# brick_i2c_3axis_MMA8451.net
KiCad netlist of a schematic drawn in EAGLE
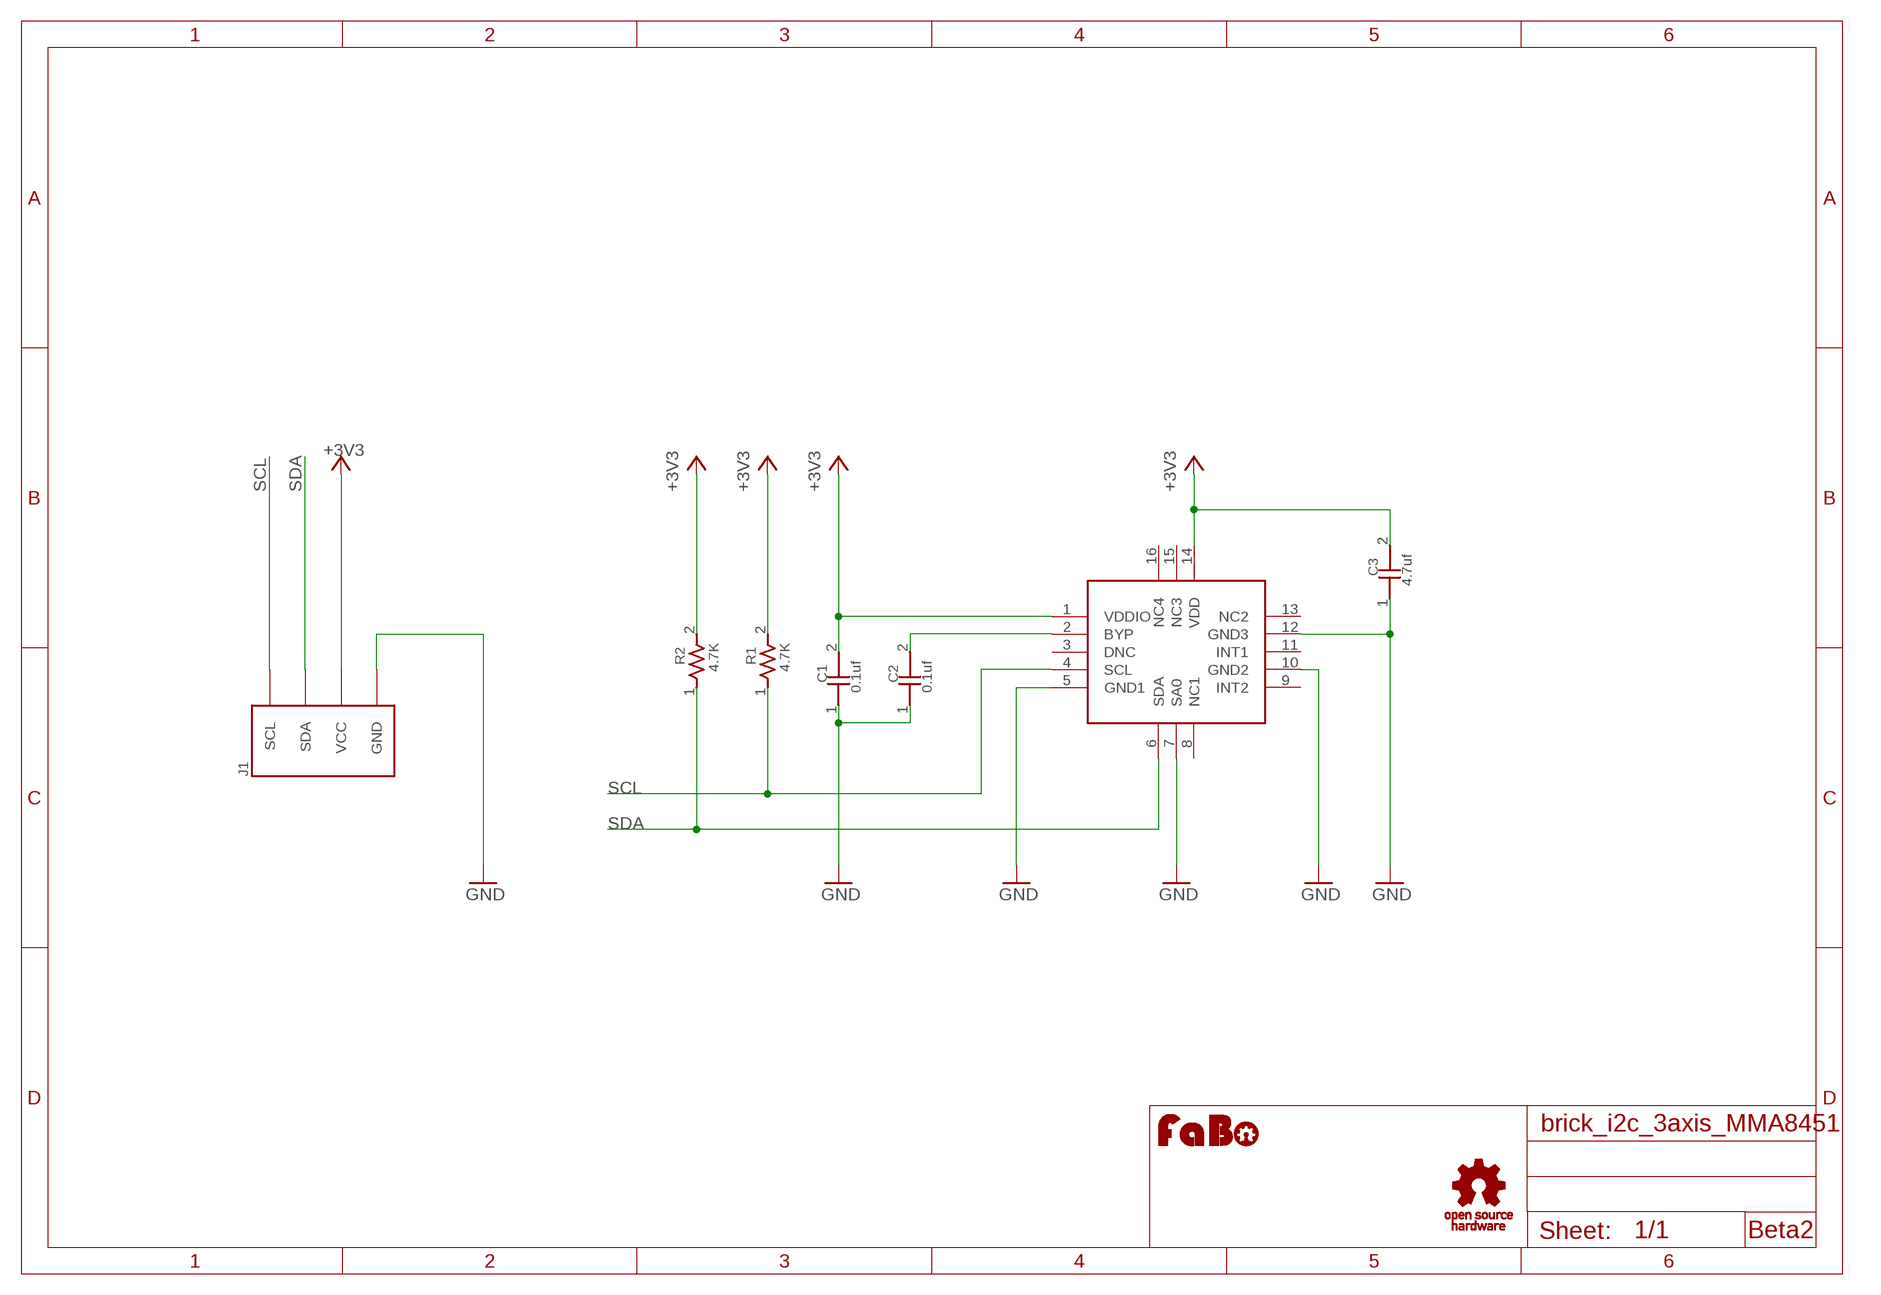
[diagram p0: schematic, sheet 1]

(export (version "E")
  (design (tool "Eeschema 10.0.6"))
  (components
    (comp (ref "C1")
      (value "0.1uf")
      (footprint "eagle-import:0603")
      (libsource (lib "eagle-import") (part "CAPACITOR0603"))
    )
    (comp (ref "C2")
      (value "0.1uf")
      (footprint "eagle-import:0603")
      (libsource (lib "eagle-import") (part "CAPACITOR0603"))
    )
    (comp (ref "C3")
      (value "4.7uf")
      (footprint "eagle-import:0603")
      (libsource (lib "eagle-import") (part "CAPACITOR0603"))
    )
    (comp (ref "J1")
      (value "BRICK_I2C")
      (footprint "eagle-import:BRICK_I2C")
      (libsource (lib "eagle-import") (part "BRICK_I2C"))
    )
    (comp (ref "MMA1")
      (value "FREESCALE-MMA8451Q")
      (footprint "eagle-import:FREESCALE-MMA8451Q")
      (libsource (lib "eagle-import") (part "FREESCALE-MMA8451Q"))
    )
    (comp (ref "R1")
      (value "4.7K")
      (footprint "eagle-import:0603")
      (libsource (lib "eagle-import") (part "RESISTOR0603"))
    )
    (comp (ref "R2")
      (value "4.7K")
      (footprint "eagle-import:0603")
      (libsource (lib "eagle-import") (part "RESISTOR0603"))
    )
    (comp (ref "U$1")
      (value "LOGO_OSHW_T-M")
      (footprint "eagle-import:LOGO_OSHW_T_M")
      (libsource (lib "eagle-import") (part "LOGO_OSHW_T-M"))
    )
    (comp (ref "U$3")
      (value "LOGO_FABO-M")
      (footprint "eagle-import:LOGO_FABO_M")
      (libsource (lib "eagle-import") (part "LOGO_FABO-M"))
    )
  )
  (nets
    (net (code "1") (name "+3V3") (class "Default")
      (node (ref "C1") (pin "2") (pinfunction "2_2") (pintype "passive"))
      (node (ref "C3") (pin "2") (pinfunction "2_2") (pintype "passive"))
      (node (ref "J1") (pin "VCC") (pinfunction "VCC_VCC") (pintype "bidirectional"))
      (node (ref "MMA1") (pin "1") (pinfunction "VDDIO_1") (pintype "bidirectional"))
      (node (ref "MMA1") (pin "14") (pinfunction "VDD_14") (pintype "bidirectional"))
      (node (ref "R1") (pin "2") (pinfunction "2_2") (pintype "passive"))
      (node (ref "R2") (pin "2") (pinfunction "2_2") (pintype "passive"))
    )
    (net (code "2") (name "/SCL") (class "Default")
      (node (ref "J1") (pin "SCL") (pinfunction "SCL_SCL") (pintype "bidirectional"))
      (node (ref "MMA1") (pin "4") (pinfunction "SCL_4") (pintype "bidirectional"))
      (node (ref "R1") (pin "1") (pinfunction "1_1") (pintype "passive"))
    )
    (net (code "3") (name "/SDA") (class "Default")
      (node (ref "J1") (pin "SDA") (pinfunction "SDA_SDA") (pintype "bidirectional"))
      (node (ref "MMA1") (pin "6") (pinfunction "SDA_6") (pintype "bidirectional"))
      (node (ref "R2") (pin "1") (pinfunction "1_1") (pintype "passive"))
    )
    (net (code "4") (name "GND") (class "Default")
      (node (ref "C1") (pin "1") (pinfunction "1_1") (pintype "passive"))
      (node (ref "C2") (pin "1") (pinfunction "1_1") (pintype "passive"))
      (node (ref "C3") (pin "1") (pinfunction "1_1") (pintype "passive"))
      (node (ref "J1") (pin "GND") (pinfunction "GND_GND") (pintype "bidirectional"))
      (node (ref "MMA1") (pin "10") (pinfunction "GND2_10") (pintype "bidirectional"))
      (node (ref "MMA1") (pin "12") (pinfunction "GND3_12") (pintype "bidirectional"))
      (node (ref "MMA1") (pin "5") (pinfunction "GND1_5") (pintype "bidirectional"))
      (node (ref "MMA1") (pin "7") (pinfunction "SA0_7") (pintype "bidirectional"))
    )
    (net (code "5") (name "Net-(MMA1-BYP)") (class "Default")
      (node (ref "C2") (pin "2") (pinfunction "2_2") (pintype "passive"))
      (node (ref "MMA1") (pin "2") (pinfunction "BYP_2") (pintype "bidirectional"))
    )
    (net (code "6") (name "unconnected-(MMA1-DNC-Pad3)") (class "Default")
      (node (ref "MMA1") (pin "3") (pinfunction "DNC_3") (pintype "bidirectional"))
    )
    (net (code "7") (name "unconnected-(MMA1-INT1-Pad11)") (class "Default")
      (node (ref "MMA1") (pin "11") (pinfunction "INT1_11") (pintype "bidirectional"))
    )
    (net (code "8") (name "unconnected-(MMA1-INT2-Pad9)") (class "Default")
      (node (ref "MMA1") (pin "9") (pinfunction "INT2_9") (pintype "bidirectional"))
    )
    (net (code "9") (name "unconnected-(MMA1-NC1-Pad8)") (class "Default")
      (node (ref "MMA1") (pin "8") (pinfunction "NC1_8") (pintype "bidirectional"))
    )
    (net (code "10") (name "unconnected-(MMA1-NC2-Pad13)") (class "Default")
      (node (ref "MMA1") (pin "13") (pinfunction "NC2_13") (pintype "bidirectional"))
    )
    (net (code "11") (name "unconnected-(MMA1-NC3-Pad15)") (class "Default")
      (node (ref "MMA1") (pin "15") (pinfunction "NC3_15") (pintype "bidirectional"))
    )
    (net (code "12") (name "unconnected-(MMA1-NC4-Pad16)") (class "Default")
      (node (ref "MMA1") (pin "16") (pinfunction "NC4_16") (pintype "bidirectional"))
    )
  )
)
